# SCH_555-Circuit_2025-03-12.net
KiCad netlist of a schematic drawn in EasyEDA
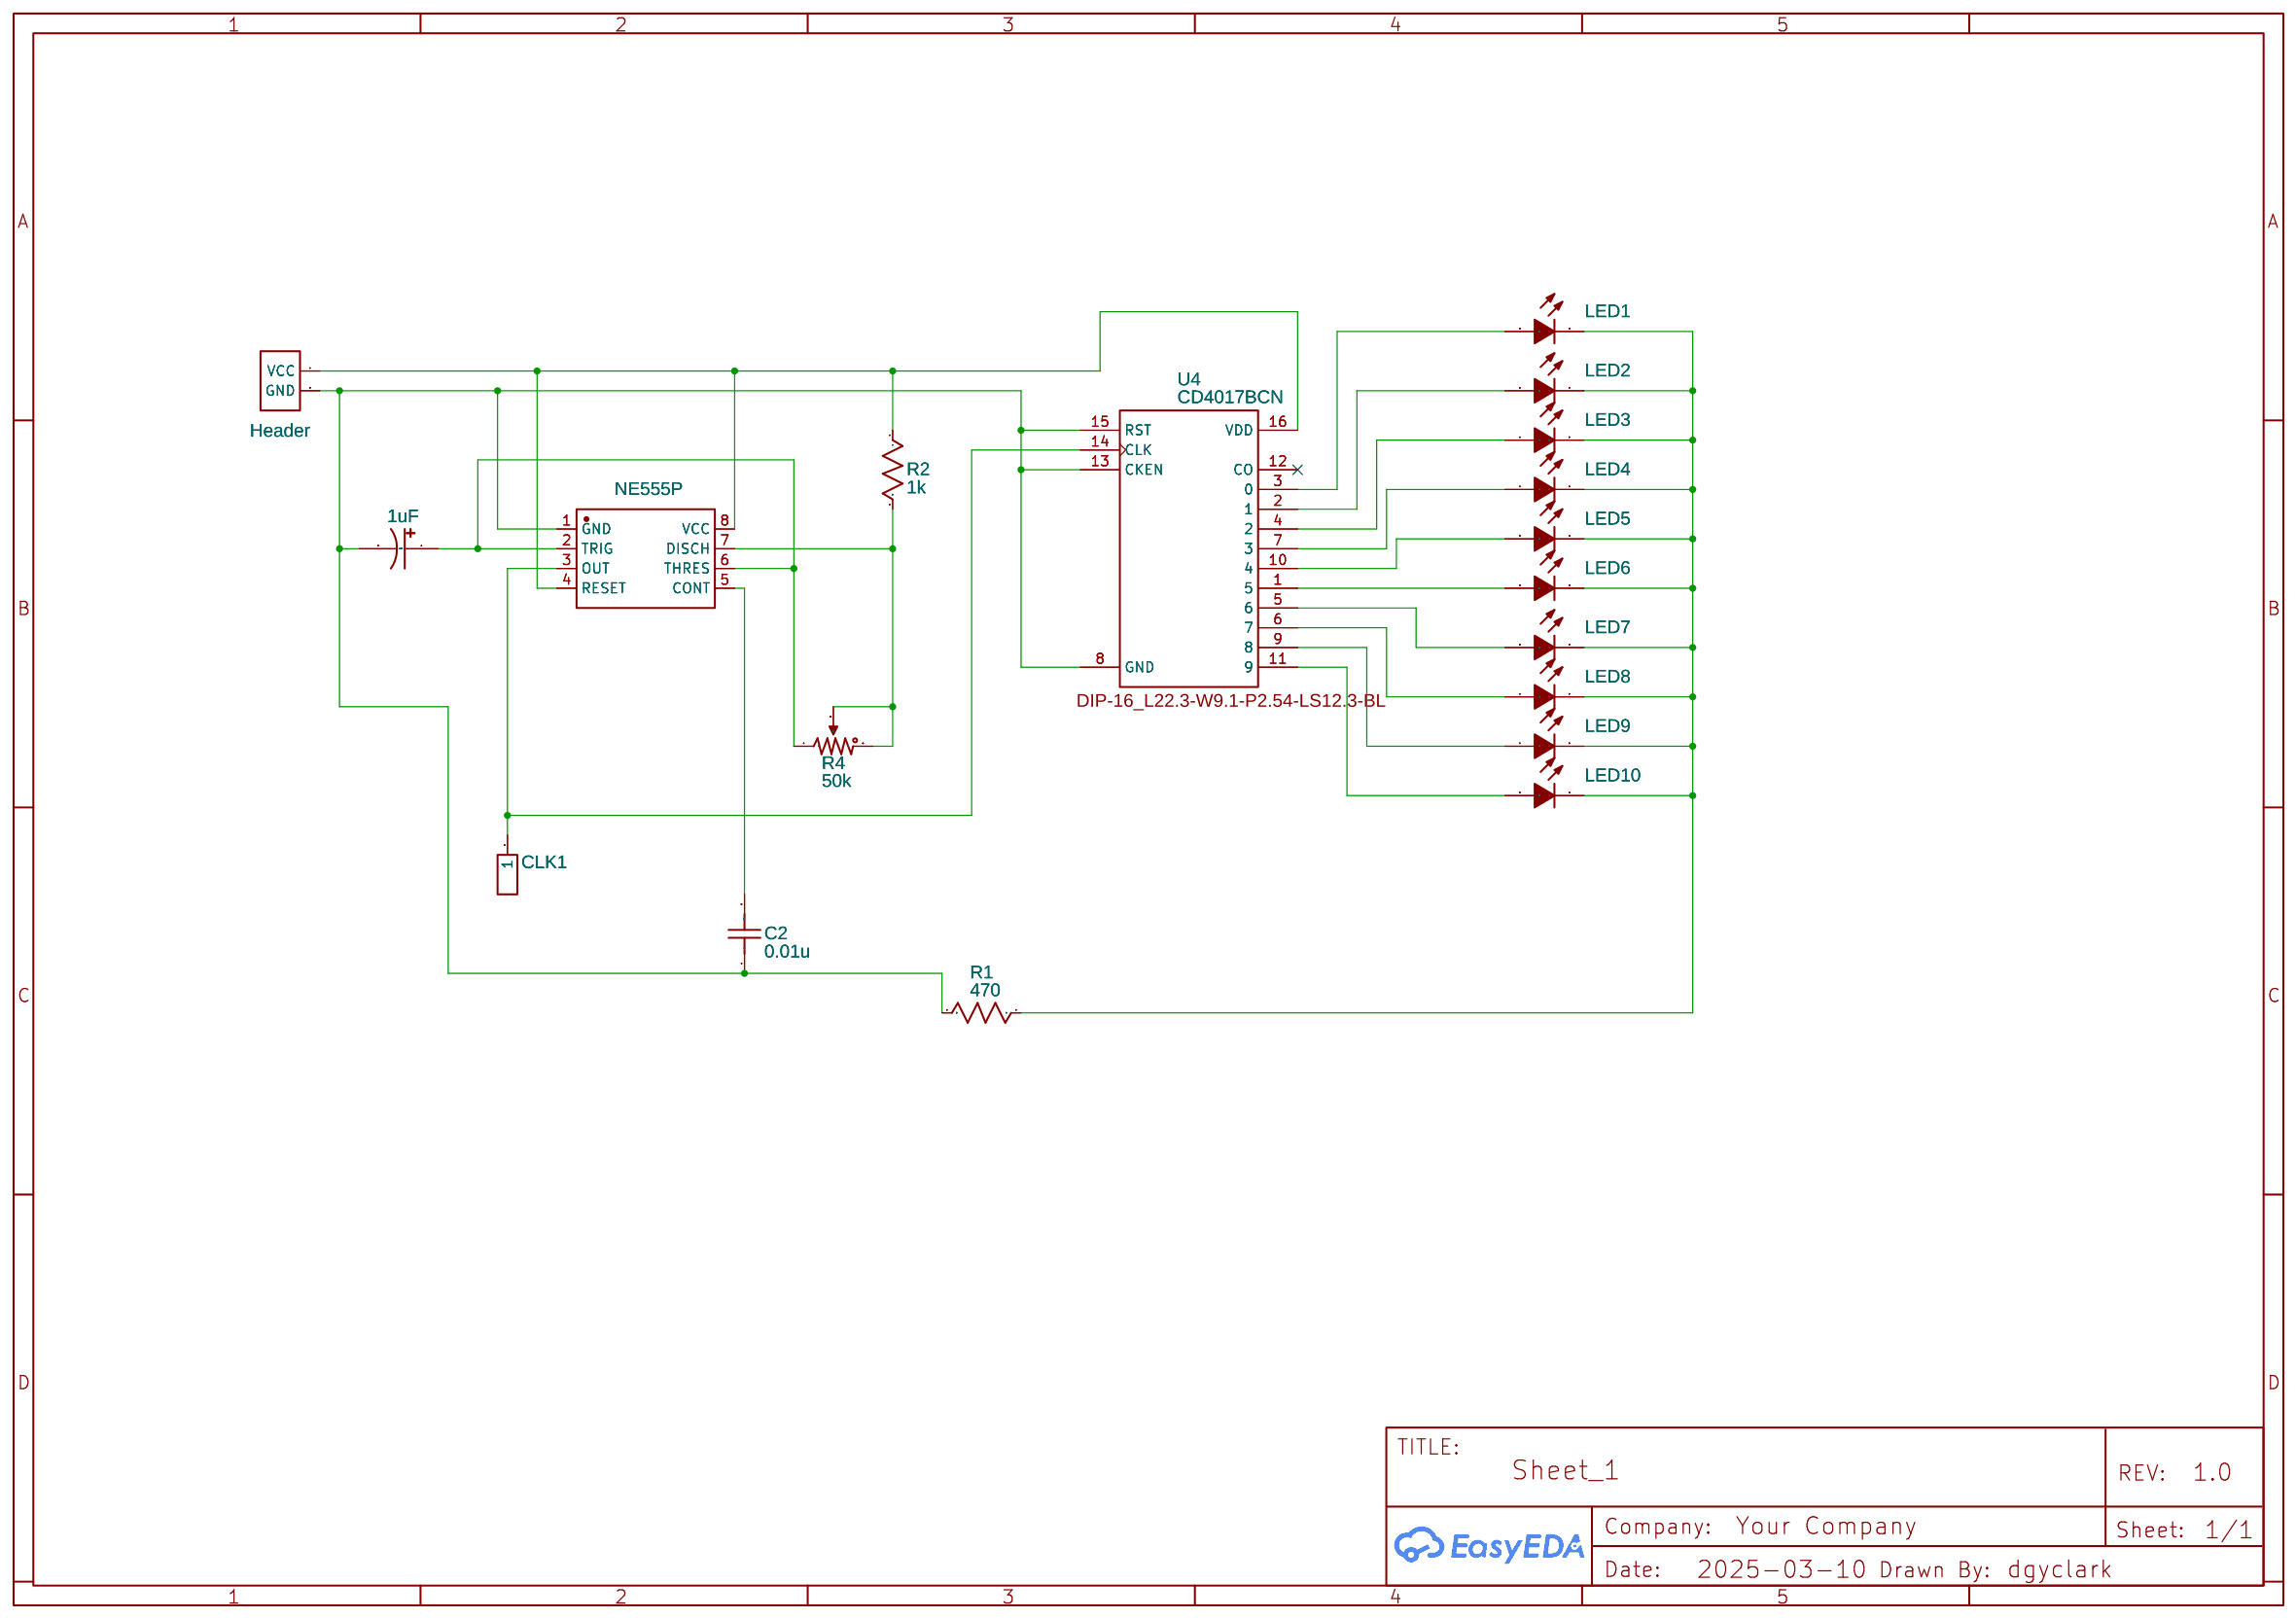
[diagram p0: schematic sheet]

(export (version "E")
  (design (tool "Eeschema 10.0.6"))
  (components
    (comp (ref "C1")
      (value "1uF")
      (fields (field (name "Manufacturer Part") "UVZ1H010MDD") (field (name "Manufacturer") "Nichicon(尼吉康)"))
      (libsource (lib "") (part "UVZ1H010MDD"))
    )
    (comp (ref "C2") (value "0.01u") (libsource (lib "") (part "C_0603_US")))
    (comp (ref "CLK1")
      (value "C81276")
      (fields
        (field (name "Manufacturer Part") "2.54-1*1P针")
        (field (name "Manufacturer") "BOOMELE(Boom Precision Elec)")
      )
      (libsource (lib "") (part "Header-Male-2.54_1x1"))
    )
    (comp (ref "H1") (value "Header") (libsource (lib "") (part "HEADER-FEMALE-2.54_1X2")))
    (comp (ref "LED1") (value "LED_5MM") (libsource (lib "") (part "LED_5MM")))
    (comp (ref "LED2") (value "LED_5MM") (libsource (lib "") (part "LED_5MM")))
    (comp (ref "LED3") (value "LED_5MM") (libsource (lib "") (part "LED_5MM")))
    (comp (ref "LED4") (value "LED_5MM") (libsource (lib "") (part "LED_5MM")))
    (comp (ref "LED5") (value "LED_5MM") (libsource (lib "") (part "LED_5MM")))
    (comp (ref "LED6") (value "LED_5MM") (libsource (lib "") (part "LED_5MM")))
    (comp (ref "LED7") (value "LED_5MM") (libsource (lib "") (part "LED_5MM")))
    (comp (ref "LED8") (value "LED_5MM") (libsource (lib "") (part "LED_5MM")))
    (comp (ref "LED9") (value "LED_5MM") (libsource (lib "") (part "LED_5MM")))
    (comp (ref "LED10") (value "LED_5MM") (libsource (lib "") (part "LED_5MM")))
    (comp (ref "R1")
      (value "470")
      (fields (field (name "Manufacturer Part") "?"))
      (libsource (lib "") (part "Resistor"))
    )
    (comp (ref "R2")
      (value "1k")
      (fields (field (name "Manufacturer Part") "?"))
      (libsource (lib "") (part "Resistor_1"))
    )
    (comp (ref "R4")
      (value "50k")
      (fields (field (name "Manufacturer Part") "?"))
      (libsource (lib "") (part "Potentiometer"))
    )
    (comp (ref "U2")
      (value "NE555P")
      (fields (field (name "Manufacturer") "TI(德州仪器)"))
      (libsource (lib "") (part "NE555P"))
    )
    (comp (ref "U4") (value "CD4017BCN") (libsource (lib "") (part "CD4017BCN")))
  )
  (nets
    (net (code "1") (name "Net-(H1-GND)") (class "Default")
      (node (ref "C1") (pin "2") (pinfunction "2_2") (pintype "unspecified"))
      (node (ref "C2") (pin "1") (pinfunction "1_1") (pintype "unspecified"))
      (node (ref "H1") (pin "2") (pinfunction "GND_2") (pintype "unspecified"))
      (node (ref "R1") (pin "2") (pinfunction "2_2") (pintype "unspecified"))
      (node (ref "U2") (pin "1") (pinfunction "GND_1") (pintype "unspecified"))
      (node (ref "U4") (pin "13") (pinfunction "CKEN_13") (pintype "unspecified"))
      (node (ref "U4") (pin "15") (pinfunction "RST_15") (pintype "unspecified"))
      (node (ref "U4") (pin "8") (pinfunction "GND_8") (pintype "passive"))
    )
    (net (code "2") (name "Net-(H1-VCC)") (class "Default")
      (node (ref "H1") (pin "1") (pinfunction "VCC_1") (pintype "unspecified"))
      (node (ref "R2") (pin "1") (pinfunction "1_1") (pintype "unspecified"))
      (node (ref "U2") (pin "4") (pinfunction "RESET_4") (pintype "unspecified"))
      (node (ref "U2") (pin "8") (pinfunction "VCC_8") (pintype "unspecified"))
      (node (ref "U4") (pin "16") (pinfunction "VDD_16") (pintype "passive"))
    )
    (net (code "3") (name "Net-(LED1-A)") (class "Default")
      (node (ref "LED1") (pin "1") (pinfunction "A_1") (pintype "input"))
      (node (ref "U4") (pin "3") (pinfunction "0_3") (pintype "output"))
    )
    (net (code "4") (name "Net-(LED1-K)") (class "Default")
      (node (ref "LED1") (pin "2") (pinfunction "K_2") (pintype "input"))
      (node (ref "LED10") (pin "2") (pinfunction "K_2") (pintype "input"))
      (node (ref "LED2") (pin "2") (pinfunction "K_2") (pintype "input"))
      (node (ref "LED3") (pin "2") (pinfunction "K_2") (pintype "input"))
      (node (ref "LED4") (pin "2") (pinfunction "K_2") (pintype "input"))
      (node (ref "LED5") (pin "2") (pinfunction "K_2") (pintype "input"))
      (node (ref "LED6") (pin "2") (pinfunction "K_2") (pintype "input"))
      (node (ref "LED7") (pin "2") (pinfunction "K_2") (pintype "input"))
      (node (ref "LED8") (pin "2") (pinfunction "K_2") (pintype "input"))
      (node (ref "LED9") (pin "2") (pinfunction "K_2") (pintype "input"))
      (node (ref "R1") (pin "1") (pinfunction "1_1") (pintype "unspecified"))
    )
    (net (code "5") (name "Net-(LED2-A)") (class "Default")
      (node (ref "LED2") (pin "1") (pinfunction "A_1") (pintype "input"))
      (node (ref "U4") (pin "2") (pinfunction "1_2") (pintype "output"))
    )
    (net (code "6") (name "Net-(LED3-A)") (class "Default")
      (node (ref "LED3") (pin "1") (pinfunction "A_1") (pintype "input"))
      (node (ref "U4") (pin "4") (pinfunction "2_4") (pintype "output"))
    )
    (net (code "7") (name "Net-(LED4-A)") (class "Default")
      (node (ref "LED4") (pin "1") (pinfunction "A_1") (pintype "input"))
      (node (ref "U4") (pin "7") (pinfunction "3_7") (pintype "output"))
    )
    (net (code "8") (name "Net-(LED5-A)") (class "Default")
      (node (ref "LED5") (pin "1") (pinfunction "A_1") (pintype "input"))
      (node (ref "U4") (pin "10") (pinfunction "4_10") (pintype "output"))
    )
    (net (code "9") (name "Net-(LED6-A)") (class "Default")
      (node (ref "LED6") (pin "1") (pinfunction "A_1") (pintype "input"))
      (node (ref "U4") (pin "1") (pinfunction "5_1") (pintype "output"))
    )
    (net (code "10") (name "Net-(LED7-A)") (class "Default")
      (node (ref "LED7") (pin "1") (pinfunction "A_1") (pintype "input"))
      (node (ref "U4") (pin "5") (pinfunction "6_5") (pintype "output"))
    )
    (net (code "11") (name "Net-(LED8-A)") (class "Default")
      (node (ref "LED8") (pin "1") (pinfunction "A_1") (pintype "input"))
      (node (ref "U4") (pin "6") (pinfunction "7_6") (pintype "output"))
    )
    (net (code "12") (name "Net-(LED9-A)") (class "Default")
      (node (ref "LED9") (pin "1") (pinfunction "A_1") (pintype "input"))
      (node (ref "U4") (pin "9") (pinfunction "8_9") (pintype "output"))
    )
    (net (code "13") (name "Net-(LED10-A)") (class "Default")
      (node (ref "LED10") (pin "1") (pinfunction "A_1") (pintype "input"))
      (node (ref "U4") (pin "11") (pinfunction "9_11") (pintype "output"))
    )
    (net (code "14") (name "Net-(R4-2)") (class "Default")
      (node (ref "R2") (pin "2") (pinfunction "2_2") (pintype "unspecified"))
      (node (ref "R4") (pin "2") (pinfunction "3_2") (pintype "unspecified"))
      (node (ref "R4") (pin "3") (pinfunction "2_3") (pintype "unspecified"))
      (node (ref "U2") (pin "7") (pinfunction "DISCH_7") (pintype "unspecified"))
    )
    (net (code "15") (name "Net-(U2-CONT)") (class "Default")
      (node (ref "C2") (pin "2") (pinfunction "2_2") (pintype "unspecified"))
      (node (ref "U2") (pin "5") (pinfunction "CONT_5") (pintype "unspecified"))
    )
    (net (code "16") (name "Net-(U2-OUT)") (class "Default")
      (node (ref "CLK1") (pin "1") (pinfunction "1_1") (pintype "unspecified"))
      (node (ref "U2") (pin "3") (pinfunction "OUT_3") (pintype "unspecified"))
      (node (ref "U4") (pin "14") (pinfunction "CLK_14") (pintype "unspecified"))
    )
    (net (code "17") (name "Net-(U2-THRES)") (class "Default")
      (node (ref "C1") (pin "1") (pinfunction "1_1") (pintype "unspecified"))
      (node (ref "R4") (pin "1") (pinfunction "1_1") (pintype "unspecified"))
      (node (ref "U2") (pin "2") (pinfunction "TRIG_2") (pintype "unspecified"))
      (node (ref "U2") (pin "6") (pinfunction "THRES_6") (pintype "unspecified"))
    )
    (net (code "18") (name "unconnected-(U4-CO-Pad12)") (class "Default")
      (node (ref "U4") (pin "12") (pinfunction "CO_12") (pintype "output+no_connect"))
    )
  )
)
